# anvil_driver.net
KiCad netlist of a schematic drawn in EAGLE
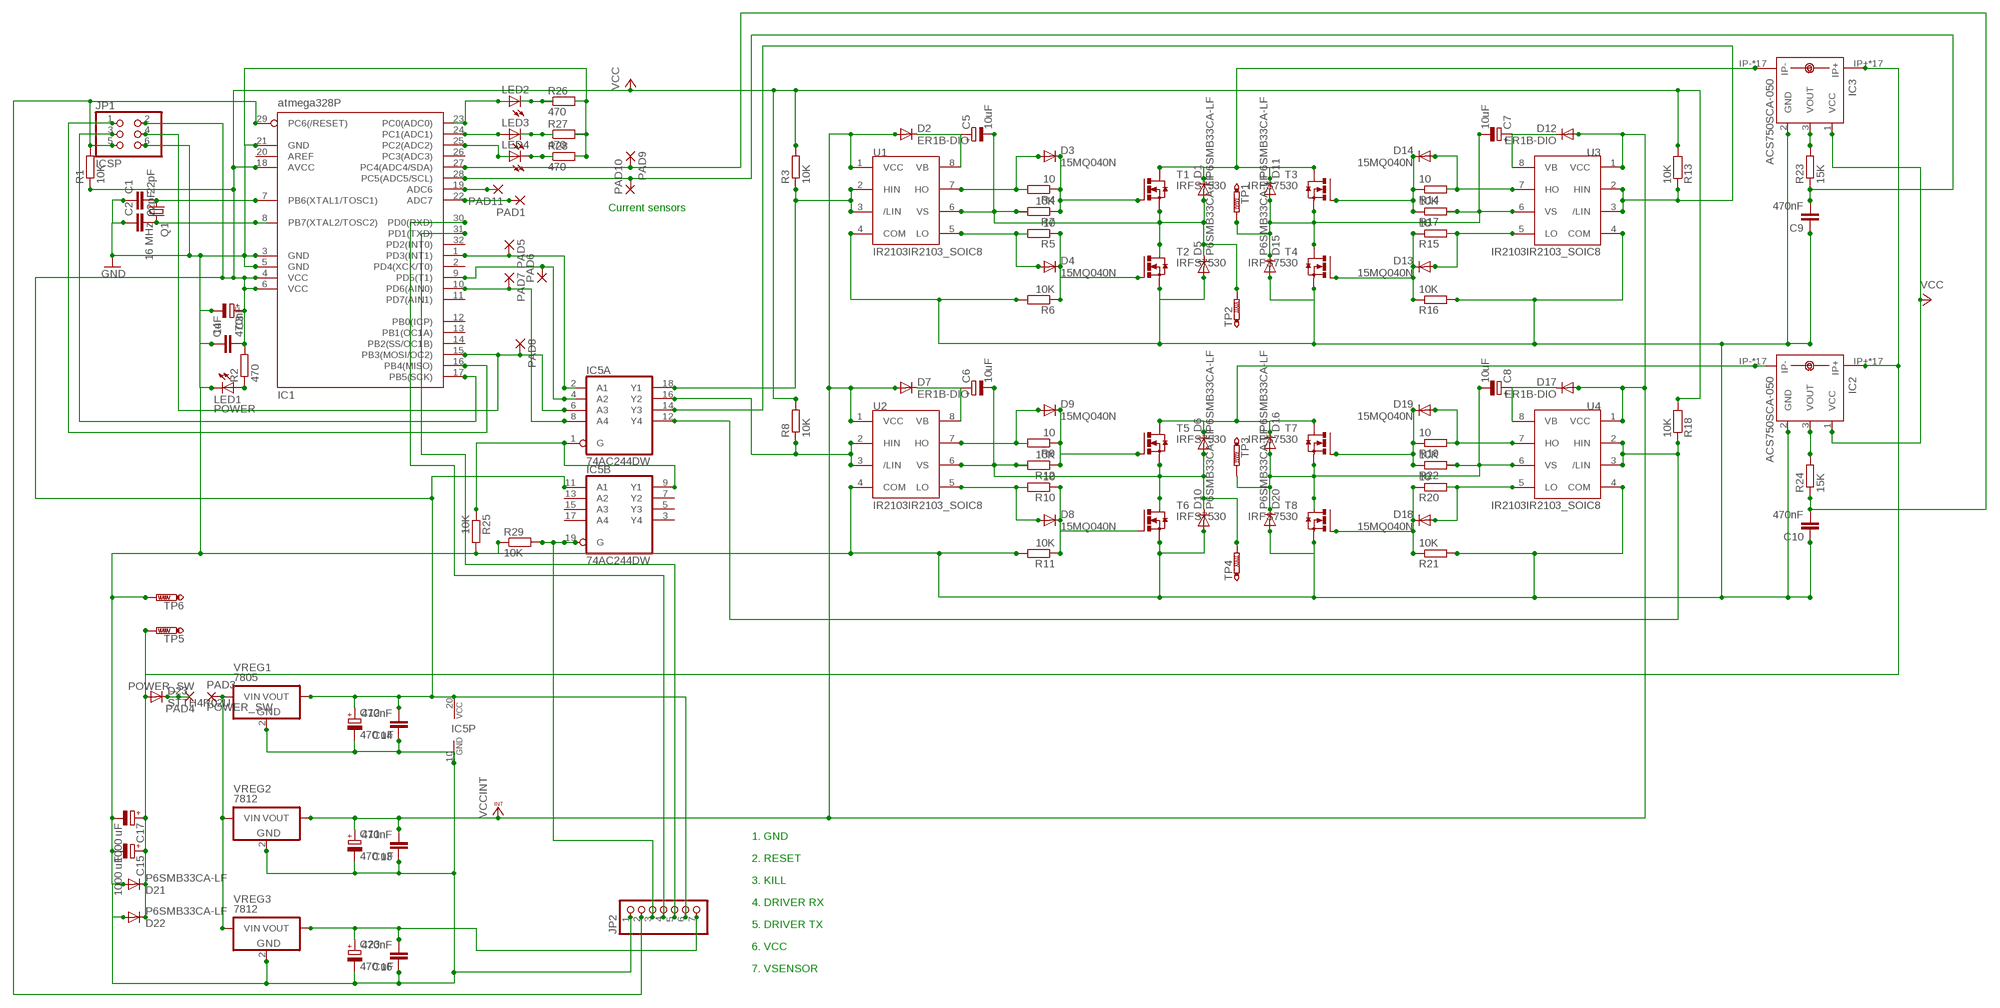
[diagram p0: schematic, sheet 1]

(export (version "E")
  (design (tool "Eeschema 10.0.6"))
  (components
    (comp (ref "C1")
      (value "22pF")
      (footprint "eagle-import:C1206")
      (libsource (lib "eagle-import") (part "C-EUC1206"))
    )
    (comp (ref "C2")
      (value "22pF")
      (footprint "eagle-import:C1206")
      (libsource (lib "eagle-import") (part "C-EUC1206"))
    )
    (comp (ref "C3")
      (value "1uF")
      (footprint "eagle-import:153CLV-0405")
      (libsource (lib "eagle-import") (part "CPOL-EU153CLV-0405"))
    )
    (comp (ref "C4")
      (value "470nF")
      (footprint "eagle-import:C1206")
      (libsource (lib "eagle-import") (part "C-EUC1206"))
    )
    (comp (ref "C5")
      (value "10uF")
      (footprint "eagle-import:153CLV-0405")
      (libsource (lib "eagle-import") (part "CPOL-EU153CLV-0405"))
    )
    (comp (ref "C6")
      (value "10uF")
      (footprint "eagle-import:153CLV-0405")
      (libsource (lib "eagle-import") (part "CPOL-EU153CLV-0405"))
    )
    (comp (ref "C7")
      (value "10uF")
      (footprint "eagle-import:153CLV-0405")
      (libsource (lib "eagle-import") (part "CPOL-EU153CLV-0405"))
    )
    (comp (ref "C8")
      (value "10uF")
      (footprint "eagle-import:153CLV-0405")
      (libsource (lib "eagle-import") (part "CPOL-EU153CLV-0405"))
    )
    (comp (ref "C9")
      (value "470nF")
      (footprint "eagle-import:C1206")
      (libsource (lib "eagle-import") (part "C-EUC1206"))
    )
    (comp (ref "C10")
      (value "470nF")
      (footprint "eagle-import:C1206")
      (libsource (lib "eagle-import") (part "C-EUC1206"))
    )
    (comp (ref "C11")
      (value "470 uF")
      (footprint "eagle-import:139CLL-2W")
      (libsource (lib "eagle-import") (part "CPOL-EU139CLL-2W"))
    )
    (comp (ref "C12")
      (value "470 uF")
      (footprint "eagle-import:139CLL-2W")
      (libsource (lib "eagle-import") (part "CPOL-EU139CLL-2W"))
    )
    (comp (ref "C13")
      (value "470nF")
      (footprint "eagle-import:C1206")
      (libsource (lib "eagle-import") (part "C-EUC1206"))
    )
    (comp (ref "C14")
      (value "470nF")
      (footprint "eagle-import:C1206")
      (libsource (lib "eagle-import") (part "C-EUC1206"))
    )
    (comp (ref "C15")
      (value "1000 uF")
      (footprint "eagle-import:139CLL-2W")
      (libsource (lib "eagle-import") (part "CPOL-EU139CLL-2W"))
    )
    (comp (ref "C16")
      (value "470nF")
      (footprint "eagle-import:C1206")
      (libsource (lib "eagle-import") (part "C-EUC1206"))
    )
    (comp (ref "C17")
      (value "1000 uF")
      (footprint "eagle-import:139CLL-2W")
      (libsource (lib "eagle-import") (part "CPOL-EU139CLL-2W"))
    )
    (comp (ref "C23")
      (value "470 uF")
      (footprint "eagle-import:139CLL-2W")
      (libsource (lib "eagle-import") (part "CPOL-EU139CLL-2W"))
    )
    (comp (ref "D1")
      (value "P6SMB33CA-LF")
      (footprint "eagle-import:DO214AA")
      (libsource (lib "eagle-import") (part "DIODE-DO214AA"))
    )
    (comp (ref "D2")
      (value "ER1B-DIO")
      (footprint "eagle-import:DO214AC")
      (libsource (lib "eagle-import") (part "DIODE-DO214AC"))
    )
    (comp (ref "D3")
      (value "15MQ040N")
      (footprint "eagle-import:DO214AC")
      (libsource (lib "eagle-import") (part "DIODE-DO214AC"))
    )
    (comp (ref "D4")
      (value "15MQ040N")
      (footprint "eagle-import:DO214AC")
      (libsource (lib "eagle-import") (part "DIODE-DO214AC"))
    )
    (comp (ref "D5")
      (value "P6SMB33CA-LF")
      (footprint "eagle-import:DO214AA")
      (libsource (lib "eagle-import") (part "DIODE-DO214AA"))
    )
    (comp (ref "D6")
      (value "P6SMB33CA-LF")
      (footprint "eagle-import:DO214AA")
      (libsource (lib "eagle-import") (part "DIODE-DO214AA"))
    )
    (comp (ref "D7")
      (value "ER1B-DIO")
      (footprint "eagle-import:DO214AC")
      (libsource (lib "eagle-import") (part "DIODE-DO214AC"))
    )
    (comp (ref "D8")
      (value "15MQ040N")
      (footprint "eagle-import:DO214AC")
      (libsource (lib "eagle-import") (part "DIODE-DO214AC"))
    )
    (comp (ref "D9")
      (value "15MQ040N")
      (footprint "eagle-import:DO214AC")
      (libsource (lib "eagle-import") (part "DIODE-DO214AC"))
    )
    (comp (ref "D10")
      (value "P6SMB33CA-LF")
      (footprint "eagle-import:DO214AA")
      (libsource (lib "eagle-import") (part "DIODE-DO214AA"))
    )
    (comp (ref "D11")
      (value "P6SMB33CA-LF")
      (footprint "eagle-import:DO214AA")
      (libsource (lib "eagle-import") (part "DIODE-DO214AA"))
    )
    (comp (ref "D12")
      (value "ER1B-DIO")
      (footprint "eagle-import:DO214AC")
      (libsource (lib "eagle-import") (part "DIODE-DO214AC"))
    )
    (comp (ref "D13")
      (value "15MQ040N")
      (footprint "eagle-import:DO214AC")
      (libsource (lib "eagle-import") (part "DIODE-DO214AC"))
    )
    (comp (ref "D14")
      (value "15MQ040N")
      (footprint "eagle-import:DO214AC")
      (libsource (lib "eagle-import") (part "DIODE-DO214AC"))
    )
    (comp (ref "D15")
      (value "P6SMB33CA-LF")
      (footprint "eagle-import:DO214AA")
      (libsource (lib "eagle-import") (part "DIODE-DO214AA"))
    )
    (comp (ref "D16")
      (value "P6SMB33CA-LF")
      (footprint "eagle-import:DO214AA")
      (libsource (lib "eagle-import") (part "DIODE-DO214AA"))
    )
    (comp (ref "D17")
      (value "ER1B-DIO")
      (footprint "eagle-import:DO214AC")
      (libsource (lib "eagle-import") (part "DIODE-DO214AC"))
    )
    (comp (ref "D18")
      (value "15MQ040N")
      (footprint "eagle-import:DO214AC")
      (libsource (lib "eagle-import") (part "DIODE-DO214AC"))
    )
    (comp (ref "D19")
      (value "15MQ040N")
      (footprint "eagle-import:DO214AC")
      (libsource (lib "eagle-import") (part "DIODE-DO214AC"))
    )
    (comp (ref "D20")
      (value "P6SMB33CA-LF")
      (footprint "eagle-import:DO214AA")
      (libsource (lib "eagle-import") (part "DIODE-DO214AA"))
    )
    (comp (ref "D21")
      (value "P6SMB33CA-LF")
      (footprint "eagle-import:DO214AA")
      (libsource (lib "eagle-import") (part "DIODE-DO214AA"))
    )
    (comp (ref "D22")
      (value "P6SMB33CA-LF")
      (footprint "eagle-import:DO214AA")
      (libsource (lib "eagle-import") (part "DIODE-DO214AA"))
    )
    (comp (ref "D23")
      (value "STTH4R02U")
      (footprint "eagle-import:DO214AA")
      (libsource (lib "eagle-import") (part "DIODE-DO214AA"))
    )
    (comp (ref "IC1")
      (value "atmega328P")
      (footprint "eagle-import:TQFP32-08")
      (fields (field (name "MPN") "ATMEGA8-16AU"))
      (libsource (lib "eagle-import") (part "MEGA8-AI"))
    )
    (comp (ref "IC2")
      (value "ACS750SCA-050")
      (footprint "eagle-import:ACS75050")
      (fields (field (name "MF") "ALLEGRO MICROSYSTEMS, INC."))
      (libsource (lib "eagle-import") (part "ACS750CA-050S"))
    )
    (comp (ref "IC3")
      (value "ACS750SCA-050")
      (footprint "eagle-import:ACS75050")
      (fields (field (name "MF") "ALLEGRO MICROSYSTEMS, INC."))
      (libsource (lib "eagle-import") (part "ACS750CA-050S"))
    )
    (comp (ref "IC5")
      (value "74AC244DW")
      (footprint "eagle-import:SO20W")
      (libsource (lib "eagle-import") (part "74244DWAC"))
    )
    (comp (ref "JP1")
      (value "ICSP")
      (footprint "eagle-import:2X03SMD")
      (libsource (lib "eagle-import") (part "PINHD-2X3_2.54-SMD"))
    )
    (comp (ref "JP2")
      (value "PINHD-1X7_2.54")
      (footprint "eagle-import:1X07")
      (libsource (lib "eagle-import") (part "PINHD-1X7_2.54"))
    )
    (comp (ref "LED1")
      (value "POWER")
      (footprint "eagle-import:1206")
      (libsource (lib "eagle-import") (part "LEDSMT1206"))
    )
    (comp (ref "LED2")
      (value "LEDSMT1206")
      (footprint "eagle-import:1206")
      (libsource (lib "eagle-import") (part "LEDSMT1206"))
    )
    (comp (ref "LED3")
      (value "LEDSMT1206")
      (footprint "eagle-import:1206")
      (libsource (lib "eagle-import") (part "LEDSMT1206"))
    )
    (comp (ref "LED4")
      (value "LEDSMT1206")
      (footprint "eagle-import:1206")
      (libsource (lib "eagle-import") (part "LEDSMT1206"))
    )
    (comp (ref "PAD1")
      (value "SMD2")
      (footprint "eagle-import:SMD1,27-2,54")
      (libsource (lib "eagle-import") (part "SMD2"))
    )
    (comp (ref "PAD3")
      (value "POWER_SW")
      (footprint "eagle-import:1,6_0,8")
      (libsource (lib "eagle-import") (part "1,6/0,8"))
    )
    (comp (ref "PAD4")
      (value "POWER_SW")
      (footprint "eagle-import:1,6_0,8")
      (libsource (lib "eagle-import") (part "1,6/0,8"))
    )
    (comp (ref "PAD5")
      (value "SMD2")
      (footprint "eagle-import:SMD1,27-2,54")
      (libsource (lib "eagle-import") (part "SMD2"))
    )
    (comp (ref "PAD6")
      (value "SMD2")
      (footprint "eagle-import:SMD1,27-2,54")
      (libsource (lib "eagle-import") (part "SMD2"))
    )
    (comp (ref "PAD7")
      (value "SMD2")
      (footprint "eagle-import:SMD1,27-2,54")
      (libsource (lib "eagle-import") (part "SMD2"))
    )
    (comp (ref "PAD8")
      (value "SMD2")
      (footprint "eagle-import:SMD1,27-2,54")
      (libsource (lib "eagle-import") (part "SMD2"))
    )
    (comp (ref "PAD9")
      (value "SMD2")
      (footprint "eagle-import:SMD1,27-2,54")
      (libsource (lib "eagle-import") (part "SMD2"))
    )
    (comp (ref "PAD10")
      (value "SMD2")
      (footprint "eagle-import:SMD1,27-2,54")
      (libsource (lib "eagle-import") (part "SMD2"))
    )
    (comp (ref "PAD11")
      (value "SMD2")
      (footprint "eagle-import:SMD1,27-2,54")
      (libsource (lib "eagle-import") (part "SMD2"))
    )
    (comp (ref "Q1")
      (value "16 MHz")
      (footprint "eagle-import:CSM-7X-DU")
      (libsource (lib "eagle-import") (part "CSM-7X-DU"))
    )
    (comp (ref "R1")
      (value "10K")
      (footprint "eagle-import:M1206")
      (libsource (lib "eagle-import") (part "R-EU_M1206"))
    )
    (comp (ref "R2")
      (value "470")
      (footprint "eagle-import:M1206")
      (libsource (lib "eagle-import") (part "R-EU_M1206"))
    )
    (comp (ref "R3")
      (value "10K")
      (footprint "eagle-import:M1206")
      (libsource (lib "eagle-import") (part "R-EU_M1206"))
    )
    (comp (ref "R4")
      (value "10")
      (footprint "eagle-import:M1206")
      (libsource (lib "eagle-import") (part "R-EU_M1206"))
    )
    (comp (ref "R5")
      (value "10")
      (footprint "eagle-import:M1206")
      (libsource (lib "eagle-import") (part "R-EU_M1206"))
    )
    (comp (ref "R6")
      (value "10K")
      (footprint "eagle-import:M1206")
      (libsource (lib "eagle-import") (part "R-EU_M1206"))
    )
    (comp (ref "R7")
      (value "10K")
      (footprint "eagle-import:M1206")
      (libsource (lib "eagle-import") (part "R-EU_M1206"))
    )
    (comp (ref "R8")
      (value "10K")
      (footprint "eagle-import:M1206")
      (libsource (lib "eagle-import") (part "R-EU_M1206"))
    )
    (comp (ref "R9")
      (value "10")
      (footprint "eagle-import:M1206")
      (libsource (lib "eagle-import") (part "R-EU_M1206"))
    )
    (comp (ref "R10")
      (value "10")
      (footprint "eagle-import:M1206")
      (libsource (lib "eagle-import") (part "R-EU_M1206"))
    )
    (comp (ref "R11")
      (value "10K")
      (footprint "eagle-import:M1206")
      (libsource (lib "eagle-import") (part "R-EU_M1206"))
    )
    (comp (ref "R12")
      (value "10K")
      (footprint "eagle-import:M1206")
      (libsource (lib "eagle-import") (part "R-EU_M1206"))
    )
    (comp (ref "R13")
      (value "10K")
      (footprint "eagle-import:M1206")
      (libsource (lib "eagle-import") (part "R-EU_M1206"))
    )
    (comp (ref "R14")
      (value "10")
      (footprint "eagle-import:M1206")
      (libsource (lib "eagle-import") (part "R-EU_M1206"))
    )
    (comp (ref "R15")
      (value "10")
      (footprint "eagle-import:M1206")
      (libsource (lib "eagle-import") (part "R-EU_M1206"))
    )
    (comp (ref "R16")
      (value "10K")
      (footprint "eagle-import:M1206")
      (libsource (lib "eagle-import") (part "R-EU_M1206"))
    )
    (comp (ref "R17")
      (value "10K")
      (footprint "eagle-import:M1206")
      (libsource (lib "eagle-import") (part "R-EU_M1206"))
    )
    (comp (ref "R18")
      (value "10K")
      (footprint "eagle-import:M1206")
      (libsource (lib "eagle-import") (part "R-EU_M1206"))
    )
    (comp (ref "R19")
      (value "10")
      (footprint "eagle-import:M1206")
      (libsource (lib "eagle-import") (part "R-EU_M1206"))
    )
    (comp (ref "R20")
      (value "10")
      (footprint "eagle-import:M1206")
      (libsource (lib "eagle-import") (part "R-EU_M1206"))
    )
    (comp (ref "R21")
      (value "10K")
      (footprint "eagle-import:M1206")
      (libsource (lib "eagle-import") (part "R-EU_M1206"))
    )
    (comp (ref "R22")
      (value "10K")
      (footprint "eagle-import:M1206")
      (libsource (lib "eagle-import") (part "R-EU_M1206"))
    )
    (comp (ref "R23")
      (value "15K")
      (footprint "eagle-import:M1206")
      (libsource (lib "eagle-import") (part "R-EU_M1206"))
    )
    (comp (ref "R24")
      (value "15K")
      (footprint "eagle-import:M1206")
      (libsource (lib "eagle-import") (part "R-EU_M1206"))
    )
    (comp (ref "R25")
      (value "10K")
      (footprint "eagle-import:M1206")
      (libsource (lib "eagle-import") (part "R-EU_M1206"))
    )
    (comp (ref "R26")
      (value "470")
      (footprint "eagle-import:M1206")
      (libsource (lib "eagle-import") (part "R-EU_M1206"))
    )
    (comp (ref "R27")
      (value "470")
      (footprint "eagle-import:M1206")
      (libsource (lib "eagle-import") (part "R-EU_M1206"))
    )
    (comp (ref "R28")
      (value "470")
      (footprint "eagle-import:M1206")
      (libsource (lib "eagle-import") (part "R-EU_M1206"))
    )
    (comp (ref "R29")
      (value "10K")
      (footprint "eagle-import:M1206")
      (libsource (lib "eagle-import") (part "R-EU_M1206"))
    )
    (comp (ref "T1")
      (value "IRFS7530")
      (footprint "eagle-import:DDPAK7")
      (libsource (lib "eagle-import") (part "IRF3805S"))
    )
    (comp (ref "T2")
      (value "IRFS7530")
      (footprint "eagle-import:DDPAK7")
      (libsource (lib "eagle-import") (part "IRF3805S"))
    )
    (comp (ref "T3")
      (value "IRFS7530")
      (footprint "eagle-import:DDPAK7")
      (libsource (lib "eagle-import") (part "IRF3805S"))
    )
    (comp (ref "T4")
      (value "IRFS7530")
      (footprint "eagle-import:DDPAK7")
      (libsource (lib "eagle-import") (part "IRF3805S"))
    )
    (comp (ref "T5")
      (value "IRFS7530")
      (footprint "eagle-import:DDPAK7")
      (libsource (lib "eagle-import") (part "IRF3805S"))
    )
    (comp (ref "T6")
      (value "IRFS7530")
      (footprint "eagle-import:DDPAK7")
      (libsource (lib "eagle-import") (part "IRF3805S"))
    )
    (comp (ref "T7")
      (value "IRFS7530")
      (footprint "eagle-import:DDPAK7")
      (libsource (lib "eagle-import") (part "IRF3805S"))
    )
    (comp (ref "T8")
      (value "IRFS7530")
      (footprint "eagle-import:DDPAK7")
      (libsource (lib "eagle-import") (part "IRF3805S"))
    )
    (comp (ref "TP1")
      (value "PTR1PAD1-20")
      (footprint "eagle-import:P1-20")
      (libsource (lib "eagle-import") (part "PTR1PAD1-20"))
    )
    (comp (ref "TP2")
      (value "PTR1PAD1-20")
      (footprint "eagle-import:P1-20")
      (libsource (lib "eagle-import") (part "PTR1PAD1-20"))
    )
    (comp (ref "TP3")
      (value "PTR1PAD1-20")
      (footprint "eagle-import:P1-20")
      (libsource (lib "eagle-import") (part "PTR1PAD1-20"))
    )
    (comp (ref "TP4")
      (value "PTR1PAD1-20")
      (footprint "eagle-import:P1-20")
      (libsource (lib "eagle-import") (part "PTR1PAD1-20"))
    )
    (comp (ref "TP5")
      (value "PTR1PAD1-20")
      (footprint "eagle-import:P1-20")
      (libsource (lib "eagle-import") (part "PTR1PAD1-20"))
    )
    (comp (ref "TP6")
      (value "PTR1PAD1-20")
      (footprint "eagle-import:P1-20")
      (libsource (lib "eagle-import") (part "PTR1PAD1-20"))
    )
    (comp (ref "U1")
      (value "IR2103IR2103_SOIC8")
      (footprint "eagle-import:SO08")
      (libsource (lib "eagle-import") (part "IR2103IR2103_SOIC8"))
    )
    (comp (ref "U2")
      (value "IR2103IR2103_SOIC8")
      (footprint "eagle-import:SO08")
      (libsource (lib "eagle-import") (part "IR2103IR2103_SOIC8"))
    )
    (comp (ref "U3")
      (value "IR2103IR2103_SOIC8")
      (footprint "eagle-import:SO08")
      (libsource (lib "eagle-import") (part "IR2103IR2103_SOIC8"))
    )
    (comp (ref "U4")
      (value "IR2103IR2103_SOIC8")
      (footprint "eagle-import:SO08")
      (libsource (lib "eagle-import") (part "IR2103IR2103_SOIC8"))
    )
    (comp (ref "VREG1")
      (value "7805")
      (footprint "eagle-import:D2PAK")
      (libsource (lib "eagle-import") (part "VREG_3PINS-D2PAK"))
    )
    (comp (ref "VREG2")
      (value "7812")
      (footprint "eagle-import:D2PAK")
      (libsource (lib "eagle-import") (part "VREG_3PINS-D2PAK"))
    )
    (comp (ref "VREG3")
      (value "7812")
      (footprint "eagle-import:D2PAK")
      (libsource (lib "eagle-import") (part "VREG_3PINS-D2PAK"))
    )
  )
  (nets
    (net (code "1") (name "/VB_1") (class "Default")
      (node (ref "C5") (pin "+") (pinfunction "+_+") (pintype "passive"))
      (node (ref "D2") (pin "C") (pinfunction "C_C") (pintype "passive"))
      (node (ref "U1") (pin "8") (pinfunction "VB_8") (pintype "power_in"))
    )
    (net (code "2") (name "/VB_2") (class "Default")
      (node (ref "C7") (pin "+") (pinfunction "+_+") (pintype "passive"))
      (node (ref "D12") (pin "C") (pinfunction "C_C") (pintype "passive"))
      (node (ref "U3") (pin "8") (pinfunction "VB_8") (pintype "power_in"))
    )
    (net (code "3") (name "/VB_3") (class "Default")
      (node (ref "C8") (pin "+") (pinfunction "+_+") (pintype "passive"))
      (node (ref "D17") (pin "C") (pinfunction "C_C") (pintype "passive"))
      (node (ref "U4") (pin "8") (pinfunction "VB_8") (pintype "power_in"))
    )
    (net (code "4") (name "/VB_4") (class "Default")
      (node (ref "C6") (pin "+") (pinfunction "+_+") (pintype "passive"))
      (node (ref "D7") (pin "C") (pinfunction "C_C") (pintype "passive"))
      (node (ref "U2") (pin "8") (pinfunction "VB_8") (pintype "power_in"))
    )
    (net (code "5") (name "GND") (class "Default")
      (node (ref "C1") (pin "1") (pinfunction "1_1") (pintype "passive"))
      (node (ref "C10") (pin "1") (pinfunction "1_1") (pintype "passive"))
      (node (ref "C11") (pin "-") (pinfunction "-_-") (pintype "passive"))
      (node (ref "C12") (pin "-") (pinfunction "-_-") (pintype "passive"))
      (node (ref "C13") (pin "1") (pinfunction "1_1") (pintype "passive"))
      (node (ref "C14") (pin "1") (pinfunction "1_1") (pintype "passive"))
      (node (ref "C15") (pin "-") (pinfunction "-_-") (pintype "passive"))
      (node (ref "C16") (pin "1") (pinfunction "1_1") (pintype "passive"))
      (node (ref "C17") (pin "-") (pinfunction "-_-") (pintype "passive"))
      (node (ref "C2") (pin "1") (pinfunction "1_1") (pintype "passive"))
      (node (ref "C23") (pin "-") (pinfunction "-_-") (pintype "passive"))
      (node (ref "C3") (pin "-") (pinfunction "-_-") (pintype "passive"))
      (node (ref "C4") (pin "1") (pinfunction "1_1") (pintype "passive"))
      (node (ref "C9") (pin "1") (pinfunction "1_1") (pintype "passive"))
      (node (ref "D10") (pin "A") (pinfunction "A_A") (pintype "passive"))
      (node (ref "D15") (pin "A") (pinfunction "A_A") (pintype "passive"))
      (node (ref "D20") (pin "A") (pinfunction "A_A") (pintype "passive"))
      (node (ref "D21") (pin "A") (pinfunction "A_A") (pintype "passive"))
      (node (ref "D22") (pin "A") (pinfunction "A_A") (pintype "passive"))
      (node (ref "D5") (pin "A") (pinfunction "A_A") (pintype "passive"))
      (node (ref "IC1") (pin "21") (pinfunction "GND_21") (pintype "power_in"))
      (node (ref "IC1") (pin "3") (pinfunction "GND_3") (pintype "power_in"))
      (node (ref "IC1") (pin "5") (pinfunction "GND_5") (pintype "power_in"))
      (node (ref "IC2") (pin "2") (pinfunction "GND_2") (pintype "power_in"))
      (node (ref "IC3") (pin "2") (pinfunction "GND_2") (pintype "power_in"))
      (node (ref "IC5") (pin "10") (pinfunction "GND_10") (pintype "power_in"))
      (node (ref "JP1") (pin "6") (pinfunction "6_6") (pintype "passive"))
      (node (ref "JP2") (pin "1") (pinfunction "1_1") (pintype "passive"))
      (node (ref "LED1") (pin "C") (pinfunction "C_C") (pintype "passive"))
      (node (ref "R11") (pin "2") (pinfunction "2_2") (pintype "passive"))
      (node (ref "R16") (pin "2") (pinfunction "2_2") (pintype "passive"))
      (node (ref "R21") (pin "2") (pinfunction "2_2") (pintype "passive"))
      (node (ref "R25") (pin "2") (pinfunction "2_2") (pintype "passive"))
      (node (ref "R26") (pin "2") (pinfunction "2_2") (pintype "passive"))
      (node (ref "R27") (pin "2") (pinfunction "2_2") (pintype "passive"))
      (node (ref "R28") (pin "2") (pinfunction "2_2") (pintype "passive"))
      (node (ref "R29") (pin "1") (pinfunction "1_1") (pintype "passive"))
      (node (ref "R6") (pin "2") (pinfunction "2_2") (pintype "passive"))
      (node (ref "T2") (pin "2") (pinfunction "S_2") (pintype "passive"))
      (node (ref "T2") (pin "3") (pinfunction "S_3") (pintype "passive"))
      (node (ref "T2") (pin "5") (pinfunction "S_5") (pintype "passive"))
      (node (ref "T2") (pin "6") (pinfunction "S_6") (pintype "passive"))
      (node (ref "T2") (pin "7") (pinfunction "S_7") (pintype "passive"))
      (node (ref "T4") (pin "2") (pinfunction "S_2") (pintype "passive"))
      (node (ref "T4") (pin "3") (pinfunction "S_3") (pintype "passive"))
      (node (ref "T4") (pin "5") (pinfunction "S_5") (pintype "passive"))
      (node (ref "T4") (pin "6") (pinfunction "S_6") (pintype "passive"))
      (node (ref "T4") (pin "7") (pinfunction "S_7") (pintype "passive"))
      (node (ref "T6") (pin "2") (pinfunction "S_2") (pintype "passive"))
      (node (ref "T6") (pin "3") (pinfunction "S_3") (pintype "passive"))
      (node (ref "T6") (pin "5") (pinfunction "S_5") (pintype "passive"))
      (node (ref "T6") (pin "6") (pinfunction "S_6") (pintype "passive"))
      (node (ref "T6") (pin "7") (pinfunction "S_7") (pintype "passive"))
      (node (ref "T8") (pin "2") (pinfunction "S_2") (pintype "passive"))
      (node (ref "T8") (pin "3") (pinfunction "S_3") (pintype "passive"))
      (node (ref "T8") (pin "5") (pinfunction "S_5") (pintype "passive"))
      (node (ref "T8") (pin "6") (pinfunction "S_6") (pintype "passive"))
      (node (ref "T8") (pin "7") (pinfunction "S_7") (pintype "passive"))
      (node (ref "TP6") (pin "TP") (pinfunction "TP_TP") (pintype "input"))
      (node (ref "U1") (pin "4") (pinfunction "COM_4") (pintype "power_in"))
      (node (ref "U2") (pin "4") (pinfunction "COM_4") (pintype "power_in"))
      (node (ref "U3") (pin "4") (pinfunction "COM_4") (pintype "power_in"))
      (node (ref "U4") (pin "4") (pinfunction "COM_4") (pintype "power_in"))
      (node (ref "VREG1") (pin "2") (pinfunction "GND_2") (pintype "bidirectional"))
      (node (ref "VREG2") (pin "2") (pinfunction "GND_2") (pintype "bidirectional"))
      (node (ref "VREG3") (pin "2") (pinfunction "GND_2") (pintype "bidirectional"))
    )
    (net (code "6") (name "Net-(C15-Pad+)") (class "Default")
      (node (ref "C15") (pin "+") (pinfunction "+_+") (pintype "passive"))
      (node (ref "C17") (pin "+") (pinfunction "+_+") (pintype "passive"))
      (node (ref "D21") (pin "C") (pinfunction "C_C") (pintype "passive"))
      (node (ref "D22") (pin "C") (pinfunction "C_C") (pintype "passive"))
      (node (ref "D23") (pin "A") (pinfunction "A_A") (pintype "passive"))
      (node (ref "IC2") (pin "IP+") (pinfunction "IP+_IP+") (pintype "passive"))
      (node (ref "IC2") (pin "IP+@10") (pinfunction "IP+_IP+@10") (pintype "passive"))
      (node (ref "IC2") (pin "IP+@11") (pinfunction "IP+_IP+@11") (pintype "passive"))
      (node (ref "IC2") (pin "IP+@12") (pinfunction "IP+_IP+@12") (pintype "passive"))
      (node (ref "IC2") (pin "IP+@13") (pinfunction "IP+_IP+@13") (pintype "passive"))
      (node (ref "IC2") (pin "IP+@14") (pinfunction "IP+_IP+@14") (pintype "passive"))
      (node (ref "IC2") (pin "IP+@15") (pinfunction "IP+_IP+@15") (pintype "passive"))
      (node (ref "IC2") (pin "IP+@16") (pinfunction "IP+_IP+@16") (pintype "passive"))
      (node (ref "IC2") (pin "IP+@17") (pinfunction "IP+_IP+@17") (pintype "passive"))
      (node (ref "IC2") (pin "IP+@2") (pinfunction "IP+_IP+@2") (pintype "passive"))
      (node (ref "IC2") (pin "IP+@3") (pinfunction "IP+_IP+@3") (pintype "passive"))
      (node (ref "IC2") (pin "IP+@4") (pinfunction "IP+_IP+@4") (pintype "passive"))
      (node (ref "IC2") (pin "IP+@5") (pinfunction "IP+_IP+@5") (pintype "passive"))
      (node (ref "IC2") (pin "IP+@6") (pinfunction "IP+_IP+@6") (pintype "passive"))
      (node (ref "IC2") (pin "IP+@7") (pinfunction "IP+_IP+@7") (pintype "passive"))
      (node (ref "IC2") (pin "IP+@8") (pinfunction "IP+_IP+@8") (pintype "passive"))
      (node (ref "IC2") (pin "IP+@9") (pinfunction "IP+_IP+@9") (pintype "passive"))
      (node (ref "IC3") (pin "IP+") (pinfunction "IP+_IP+") (pintype "passive"))
      (node (ref "IC3") (pin "IP+@10") (pinfunction "IP+_IP+@10") (pintype "passive"))
      (node (ref "IC3") (pin "IP+@11") (pinfunction "IP+_IP+@11") (pintype "passive"))
      (node (ref "IC3") (pin "IP+@12") (pinfunction "IP+_IP+@12") (pintype "passive"))
      (node (ref "IC3") (pin "IP+@13") (pinfunction "IP+_IP+@13") (pintype "passive"))
      (node (ref "IC3") (pin "IP+@14") (pinfunction "IP+_IP+@14") (pintype "passive"))
      (node (ref "IC3") (pin "IP+@15") (pinfunction "IP+_IP+@15") (pintype "passive"))
      (node (ref "IC3") (pin "IP+@16") (pinfunction "IP+_IP+@16") (pintype "passive"))
      (node (ref "IC3") (pin "IP+@17") (pinfunction "IP+_IP+@17") (pintype "passive"))
      (node (ref "IC3") (pin "IP+@2") (pinfunction "IP+_IP+@2") (pintype "passive"))
      (node (ref "IC3") (pin "IP+@3") (pinfunction "IP+_IP+@3") (pintype "passive"))
      (node (ref "IC3") (pin "IP+@4") (pinfunction "IP+_IP+@4") (pintype "passive"))
      (node (ref "IC3") (pin "IP+@5") (pinfunction "IP+_IP+@5") (pintype "passive"))
      (node (ref "IC3") (pin "IP+@6") (pinfunction "IP+_IP+@6") (pintype "passive"))
      (node (ref "IC3") (pin "IP+@7") (pinfunction "IP+_IP+@7") (pintype "passive"))
      (node (ref "IC3") (pin "IP+@8") (pinfunction "IP+_IP+@8") (pintype "passive"))
      (node (ref "IC3") (pin "IP+@9") (pinfunction "IP+_IP+@9") (pintype "passive"))
      (node (ref "TP5") (pin "TP") (pinfunction "TP_TP") (pintype "input"))
    )
    (net (code "7") (name "Net-(IC1-ADC6)") (class "Default")
      (node (ref "IC1") (pin "19") (pinfunction "ADC6_19") (pintype "bidirectional"))
      (node (ref "PAD11") (pin "1") (pinfunction "P_1") (pintype "passive"))
    )
    (net (code "8") (name "Net-(IC1-ADC7)") (class "Default")
      (node (ref "IC1") (pin "22") (pinfunction "ADC7_22") (pintype "bidirectional"))
      (node (ref "PAD1") (pin "1") (pinfunction "P_1") (pintype "passive"))
    )
    (net (code "9") (name "Net-(IC1-PB3(MOSI{slash}OC2))") (class "Default")
      (node (ref "IC1") (pin "15") (pinfunction "PB3(MOSI/OC2)_15") (pintype "bidirectional"))
      (node (ref "IC5") (pin "6") (pinfunction "A3_6") (pintype "input"))
      (node (ref "JP1") (pin "4") (pinfunction "4_4") (pintype "passive"))
      (node (ref "PAD8") (pin "1") (pinfunction "P_1") (pintype "passive"))
    )
    (net (code "10") (name "Net-(IC1-PB4(MISO))") (class "Default")
      (node (ref "IC1") (pin "16") (pinfunction "PB4(MISO)_16") (pintype "bidirectional"))
      (node (ref "JP1") (pin "1") (pinfunction "1_1") (pintype "passive"))
    )
    (net (code "11") (name "Net-(IC1-PB5(SCK))") (class "Default")
      (node (ref "IC1") (pin "17") (pinfunction "PB5(SCK)_17") (pintype "bidirectional"))
      (node (ref "JP1") (pin "3") (pinfunction "3_3") (pintype "passive"))
    )
    (net (code "12") (name "Net-(IC1-PB6(XTAL1{slash}TOSC1))") (class "Default")
      (node (ref "C1") (pin "2") (pinfunction "2_2") (pintype "passive"))
      (node (ref "IC1") (pin "7") (pinfunction "PB6(XTAL1/TOSC1)_7") (pintype "bidirectional"))
      (node (ref "Q1") (pin "1") (pinfunction "1_1") (pintype "passive"))
    )
    (net (code "13") (name "Net-(IC1-PB7(XTAL2{slash}TOSC2))") (class "Default")
      (node (ref "C2") (pin "2") (pinfunction "2_2") (pintype "passive"))
      (node (ref "IC1") (pin "8") (pinfunction "PB7(XTAL2/TOSC2)_8") (pintype "bidirectional"))
      (node (ref "Q1") (pin "2") (pinfunction "2_2") (pintype "passive"))
    )
    (net (code "14") (name "Net-(IC1-PC0(ADC0))") (class "Default")
      (node (ref "IC1") (pin "23") (pinfunction "PC0(ADC0)_23") (pintype "bidirectional"))
      (node (ref "LED2") (pin "A") (pinfunction "A_A") (pintype "passive"))
    )
    (net (code "15") (name "Net-(IC1-PC1(ADC1))") (class "Default")
      (node (ref "IC1") (pin "24") (pinfunction "PC1(ADC1)_24") (pintype "bidirectional"))
      (node (ref "LED3") (pin "A") (pinfunction "A_A") (pintype "passive"))
    )
    (net (code "16") (name "Net-(IC1-PC2(ADC2))") (class "Default")
      (node (ref "IC1") (pin "25") (pinfunction "PC2(ADC2)_25") (pintype "bidirectional"))
      (node (ref "LED4") (pin "A") (pinfunction "A_A") (pintype "passive"))
    )
    (net (code "17") (name "Net-(IC1-PC4(ADC4{slash}SDA))") (class "Default")
      (node (ref "C10") (pin "2") (pinfunction "2_2") (pintype "passive"))
      (node (ref "IC1") (pin "27") (pinfunction "PC4(ADC4/SDA)_27") (pintype "bidirectional"))
      (node (ref "PAD9") (pin "1") (pinfunction "P_1") (pintype "passive"))
      (node (ref "R24") (pin "1") (pinfunction "1_1") (pintype "passive"))
    )
    (net (code "18") (name "Net-(IC1-PC5(ADC5{slash}SCL))") (class "Default")
      (node (ref "C9") (pin "2") (pinfunction "2_2") (pintype "passive"))
      (node (ref "IC1") (pin "28") (pinfunction "PC5(ADC5/SCL)_28") (pintype "bidirectional"))
      (node (ref "PAD10") (pin "1") (pinfunction "P_1") (pintype "passive"))
      (node (ref "R23") (pin "1") (pinfunction "1_1") (pintype "passive"))
    )
    (net (code "19") (name "Net-(IC1-PC6({slash}RESET))") (class "Default")
      (node (ref "IC1") (pin "29") (pinfunction "PC6(/RESET)_29") (pintype "bidirectional"))
      (node (ref "JP1") (pin "5") (pinfunction "5_5") (pintype "passive"))
      (node (ref "JP2") (pin "2") (pinfunction "2_2") (pintype "passive"))
      (node (ref "R1") (pin "2") (pinfunction "2_2") (pintype "passive"))
    )
    (net (code "20") (name "Net-(IC1-PD0(RXD))") (class "Default")
      (node (ref "IC1") (pin "30") (pinfunction "PD0(RXD)_30") (pintype "bidirectional"))
      (node (ref "JP2") (pin "4") (pinfunction "4_4") (pintype "passive"))
    )
    (net (code "21") (name "Net-(IC1-PD3(INT1))") (class "Default")
      (node (ref "IC1") (pin "1") (pinfunction "PD3(INT1)_1") (pintype "bidirectional"))
      (node (ref "IC5") (pin "2") (pinfunction "A1_2") (pintype "input"))
      (node (ref "PAD5") (pin "1") (pinfunction "P_1") (pintype "passive"))
    )
    (net (code "22") (name "Net-(IC1-PD5(T1))") (class "Default")
      (node (ref "IC1") (pin "9") (pinfunction "PD5(T1)_9") (pintype "bidirectional"))
      (node (ref "IC5") (pin "4") (pinfunction "A2_4") (pintype "input"))
      (node (ref "PAD6") (pin "1") (pinfunction "P_1") (pintype "passive"))
    )
    (net (code "23") (name "Net-(IC1-PD6(AIN0))") (class "Default")
      (node (ref "IC1") (pin "10") (pinfunction "PD6(AIN0)_10") (pintype "bidirectional"))
      (node (ref "IC5") (pin "8") (pinfunction "A4_8") (pintype "input"))
      (node (ref "PAD7") (pin "1") (pinfunction "P_1") (pintype "passive"))
    )
    (net (code "24") (name "Net-(IC2-VOUT)") (class "Default")
      (node (ref "IC2") (pin "3") (pinfunction "VOUT_3") (pintype "output"))
      (node (ref "R24") (pin "2") (pinfunction "2_2") (pintype "passive"))
    )
    (net (code "25") (name "Net-(IC3-VOUT)") (class "Default")
      (node (ref "IC3") (pin "3") (pinfunction "VOUT_3") (pintype "output"))
      (node (ref "R23") (pin "2") (pinfunction "2_2") (pintype "passive"))
    )
    (net (code "26") (name "Net-(IC5A-G)") (class "Default")
      (node (ref "IC5") (pin "1") (pinfunction "G_1") (pintype "input"))
      (node (ref "IC5") (pin "9") (pinfunction "Y1_9") (pintype "tri_state"))
      (node (ref "R25") (pin "1") (pinfunction "1_1") (pintype "passive"))
    )
    (net (code "27") (name "Net-(IC5A-Y1)") (class "Default")
      (node (ref "IC5") (pin "18") (pinfunction "Y1_18") (pintype "tri_state"))
      (node (ref "R3") (pin "1") (pinfunction "1_1") (pintype "passive"))
      (node (ref "U1") (pin "2") (pinfunction "HIN_2") (pintype "input"))
      (node (ref "U1") (pin "3") (pinfunction "/LIN_3") (pintype "input"))
    )
    (net (code "28") (name "Net-(IC5A-Y2)") (class "Default")
      (node (ref "IC5") (pin "16") (pinfunction "Y2_16") (pintype "tri_state"))
      (node (ref "R8") (pin "1") (pinfunction "1_1") (pintype "passive"))
      (node (ref "U2") (pin "2") (pinfunction "HIN_2") (pintype "input"))
      (node (ref "U2") (pin "3") (pinfunction "/LIN_3") (pintype "input"))
    )
    (net (code "29") (name "Net-(IC5A-Y3)") (class "Default")
      (node (ref "IC5") (pin "14") (pinfunction "Y3_14") (pintype "tri_state"))
      (node (ref "R13") (pin "1") (pinfunction "1_1") (pintype "passive"))
      (node (ref "U3") (pin "2") (pinfunction "HIN_2") (pintype "input"))
      (node (ref "U3") (pin "3") (pinfunction "/LIN_3") (pintype "input"))
    )
    (net (code "30") (name "Net-(IC5A-Y4)") (class "Default")
      (node (ref "IC5") (pin "12") (pinfunction "Y4_12") (pintype "tri_state"))
      (node (ref "R18") (pin "1") (pinfunction "1_1") (pintype "passive"))
      (node (ref "U4") (pin "2") (pinfunction "HIN_2") (pintype "input"))
      (node (ref "U4") (pin "3") (pinfunction "/LIN_3") (pintype "input"))
    )
    (net (code "31") (name "Net-(IC5B-G)") (class "Default")
      (node (ref "IC5") (pin "19") (pinfunction "G_19") (pintype "input"))
      (node (ref "JP2") (pin "3") (pinfunction "3_3") (pintype "passive"))
      (node (ref "R29") (pin "2") (pinfunction "2_2") (pintype "passive"))
    )
    (net (code "32") (name "Net-(LED1-PadA)") (class "Default")
      (node (ref "LED1") (pin "A") (pinfunction "A_A") (pintype "passive"))
      (node (ref "R2") (pin "1") (pinfunction "1_1") (pintype "passive"))
    )
    (net (code "33") (name "Net-(LED2-PadC)") (class "Default")
      (node (ref "LED2") (pin "C") (pinfunction "C_C") (pintype "passive"))
      (node (ref "R26") (pin "1") (pinfunction "1_1") (pintype "passive"))
    )
    (net (code "34") (name "Net-(LED3-PadC)") (class "Default")
      (node (ref "LED3") (pin "C") (pinfunction "C_C") (pintype "passive"))
      (node (ref "R27") (pin "1") (pinfunction "1_1") (pintype "passive"))
    )
    (net (code "35") (name "Net-(LED4-PadC)") (class "Default")
      (node (ref "LED4") (pin "C") (pinfunction "C_C") (pintype "passive"))
      (node (ref "R28") (pin "1") (pinfunction "1_1") (pintype "passive"))
    )
    (net (code "36") (name "Net-(PAD3-P)") (class "Default")
      (node (ref "PAD3") (pin "1") (pinfunction "P_1") (pintype "passive"))
      (node (ref "VREG1") (pin "1") (pinfunction "VIN_1") (pintype "bidirectional"))
      (node (ref "VREG2") (pin "1") (pinfunction "VIN_1") (pintype "bidirectional"))
      (node (ref "VREG3") (pin "1") (pinfunction "VIN_1") (pintype "bidirectional"))
    )
    (net (code "37") (name "Net-(PAD4-P)") (class "Default")
      (node (ref "D23") (pin "C") (pinfunction "C_C") (pintype "passive"))
      (node (ref "PAD4") (pin "1") (pinfunction "P_1") (pintype "passive"))
    )
    (net (code "38") (name "Net-(T1-D)") (class "Default")
      (node (ref "D1") (pin "C") (pinfunction "C_C") (pintype "passive"))
      (node (ref "D11") (pin "C") (pinfunction "C_C") (pintype "passive"))
      (node (ref "IC3") (pin "IP-") (pinfunction "IP-_IP-") (pintype "passive"))
      (node (ref "IC3") (pin "IP-@10") (pinfunction "IP-_IP-@10") (pintype "passive"))
      (node (ref "IC3") (pin "IP-@11") (pinfunction "IP-_IP-@11") (pintype "passive"))
      (node (ref "IC3") (pin "IP-@12") (pinfunction "IP-_IP-@12") (pintype "passive"))
      (node (ref "IC3") (pin "IP-@13") (pinfunction "IP-_IP-@13") (pintype "passive"))
      (node (ref "IC3") (pin "IP-@14") (pinfunction "IP-_IP-@14") (pintype "passive"))
      (node (ref "IC3") (pin "IP-@15") (pinfunction "IP-_IP-@15") (pintype "passive"))
      (node (ref "IC3") (pin "IP-@16") (pinfunction "IP-_IP-@16") (pintype "passive"))
      (node (ref "IC3") (pin "IP-@17") (pinfunction "IP-_IP-@17") (pintype "passive"))
      (node (ref "IC3") (pin "IP-@2") (pinfunction "IP-_IP-@2") (pintype "passive"))
      (node (ref "IC3") (pin "IP-@3") (pinfunction "IP-_IP-@3") (pintype "passive"))
      (node (ref "IC3") (pin "IP-@4") (pinfunction "IP-_IP-@4") (pintype "passive"))
      (node (ref "IC3") (pin "IP-@5") (pinfunction "IP-_IP-@5") (pintype "passive"))
      (node (ref "IC3") (pin "IP-@6") (pinfunction "IP-_IP-@6") (pintype "passive"))
      (node (ref "IC3") (pin "IP-@7") (pinfunction "IP-_IP-@7") (pintype "passive"))
      (node (ref "IC3") (pin "IP-@8") (pinfunction "IP-_IP-@8") (pintype "passive"))
      (node (ref "IC3") (pin "IP-@9") (pinfunction "IP-_IP-@9") (pintype "passive"))
      (node (ref "T1") (pin "4") (pinfunction "D_4") (pintype "passive"))
      (node (ref "T3") (pin "4") (pinfunction "D_4") (pintype "passive"))
    )
    (net (code "39") (name "Net-(T1-G)") (class "Default")
      (node (ref "D3") (pin "C") (pinfunction "C_C") (pintype "passive"))
      (node (ref "R4") (pin "1") (pinfunction "1_1") (pintype "passive"))
      (node (ref "R7") (pin "1") (pinfunction "1_1") (pintype "passive"))
      (node (ref "T1") (pin "1") (pinfunction "G_1") (pintype "passive"))
    )
    (net (code "40") (name "Net-(T2-D)") (class "Default")
      (node (ref "C5") (pin "-") (pinfunction "-_-") (pintype "passive"))
      (node (ref "D1") (pin "A") (pinfunction "A_A") (pintype "passive"))
      (node (ref "D5") (pin "C") (pinfunction "C_C") (pintype "passive"))
      (node (ref "R7") (pin "2") (pinfunction "2_2") (pintype "passive"))
      (node (ref "T1") (pin "2") (pinfunction "S_2") (pintype "passive"))
      (node (ref "T1") (pin "3") (pinfunction "S_3") (pintype "passive"))
      (node (ref "T1") (pin "5") (pinfunction "S_5") (pintype "passive"))
      (node (ref "T1") (pin "6") (pinfunction "S_6") (pintype "passive"))
      (node (ref "T1") (pin "7") (pinfunction "S_7") (pintype "passive"))
      (node (ref "T2") (pin "4") (pinfunction "D_4") (pintype "passive"))
      (node (ref "TP2") (pin "TP") (pinfunction "TP_TP") (pintype "input"))
      (node (ref "U1") (pin "6") (pinfunction "VS_6") (pintype "output"))
    )
    (net (code "41") (name "Net-(T2-G)") (class "Default")
      (node (ref "D4") (pin "C") (pinfunction "C_C") (pintype "passive"))
      (node (ref "R5") (pin "1") (pinfunction "1_1") (pintype "passive"))
      (node (ref "R6") (pin "1") (pinfunction "1_1") (pintype "passive"))
      (node (ref "T2") (pin "1") (pinfunction "G_1") (pintype "passive"))
    )
    (net (code "42") (name "Net-(T3-G)") (class "Default")
      (node (ref "D14") (pin "C") (pinfunction "C_C") (pintype "passive"))
      (node (ref "R14") (pin "1") (pinfunction "1_1") (pintype "passive"))
      (node (ref "R17") (pin "1") (pinfunction "1_1") (pintype "passive"))
      (node (ref "T3") (pin "1") (pinfunction "G_1") (pintype "passive"))
    )
    (net (code "43") (name "Net-(T4-D)") (class "Default")
      (node (ref "C7") (pin "-") (pinfunction "-_-") (pintype "passive"))
      (node (ref "D11") (pin "A") (pinfunction "A_A") (pintype "passive"))
      (node (ref "D15") (pin "C") (pinfunction "C_C") (pintype "passive"))
      (node (ref "R17") (pin "2") (pinfunction "2_2") (pintype "passive"))
      (node (ref "T3") (pin "2") (pinfunction "S_2") (pintype "passive"))
      (node (ref "T3") (pin "3") (pinfunction "S_3") (pintype "passive"))
      (node (ref "T3") (pin "5") (pinfunction "S_5") (pintype "passive"))
      (node (ref "T3") (pin "6") (pinfunction "S_6") (pintype "passive"))
      (node (ref "T3") (pin "7") (pinfunction "S_7") (pintype "passive"))
      (node (ref "T4") (pin "4") (pinfunction "D_4") (pintype "passive"))
      (node (ref "TP1") (pin "TP") (pinfunction "TP_TP") (pintype "input"))
      (node (ref "U3") (pin "6") (pinfunction "VS_6") (pintype "output"))
    )
    (net (code "44") (name "Net-(T4-G)") (class "Default")
      (node (ref "D13") (pin "C") (pinfunction "C_C") (pintype "passive"))
      (node (ref "R15") (pin "1") (pinfunction "1_1") (pintype "passive"))
      (node (ref "R16") (pin "1") (pinfunction "1_1") (pintype "passive"))
      (node (ref "T4") (pin "1") (pinfunction "G_1") (pintype "passive"))
    )
    (net (code "45") (name "Net-(T5-D)") (class "Default")
      (node (ref "D16") (pin "C") (pinfunction "C_C") (pintype "passive"))
      (node (ref "D6") (pin "C") (pinfunction "C_C") (pintype "passive"))
      (node (ref "IC2") (pin "IP-") (pinfunction "IP-_IP-") (pintype "passive"))
      (node (ref "IC2") (pin "IP-@10") (pinfunction "IP-_IP-@10") (pintype "passive"))
      (node (ref "IC2") (pin "IP-@11") (pinfunction "IP-_IP-@11") (pintype "passive"))
      (node (ref "IC2") (pin "IP-@12") (pinfunction "IP-_IP-@12") (pintype "passive"))
      (node (ref "IC2") (pin "IP-@13") (pinfunction "IP-_IP-@13") (pintype "passive"))
      (node (ref "IC2") (pin "IP-@14") (pinfunction "IP-_IP-@14") (pintype "passive"))
      (node (ref "IC2") (pin "IP-@15") (pinfunction "IP-_IP-@15") (pintype "passive"))
      (node (ref "IC2") (pin "IP-@16") (pinfunction "IP-_IP-@16") (pintype "passive"))
      (node (ref "IC2") (pin "IP-@17") (pinfunction "IP-_IP-@17") (pintype "passive"))
      (node (ref "IC2") (pin "IP-@2") (pinfunction "IP-_IP-@2") (pintype "passive"))
      (node (ref "IC2") (pin "IP-@3") (pinfunction "IP-_IP-@3") (pintype "passive"))
      (node (ref "IC2") (pin "IP-@4") (pinfunction "IP-_IP-@4") (pintype "passive"))
      (node (ref "IC2") (pin "IP-@5") (pinfunction "IP-_IP-@5") (pintype "passive"))
      (node (ref "IC2") (pin "IP-@6") (pinfunction "IP-_IP-@6") (pintype "passive"))
      (node (ref "IC2") (pin "IP-@7") (pinfunction "IP-_IP-@7") (pintype "passive"))
      (node (ref "IC2") (pin "IP-@8") (pinfunction "IP-_IP-@8") (pintype "passive"))
      (node (ref "IC2") (pin "IP-@9") (pinfunction "IP-_IP-@9") (pintype "passive"))
      (node (ref "T5") (pin "4") (pinfunction "D_4") (pintype "passive"))
      (node (ref "T7") (pin "4") (pinfunction "D_4") (pintype "passive"))
    )
    (net (code "46") (name "Net-(T5-G)") (class "Default")
      (node (ref "D9") (pin "C") (pinfunction "C_C") (pintype "passive"))
      (node (ref "R12") (pin "1") (pinfunction "1_1") (pintype "passive"))
      (node (ref "R9") (pin "1") (pinfunction "1_1") (pintype "passive"))
      (node (ref "T5") (pin "1") (pinfunction "G_1") (pintype "passive"))
    )
    (net (code "47") (name "Net-(T6-D)") (class "Default")
      (node (ref "C6") (pin "-") (pinfunction "-_-") (pintype "passive"))
      (node (ref "D10") (pin "C") (pinfunction "C_C") (pintype "passive"))
      (node (ref "D6") (pin "A") (pinfunction "A_A") (pintype "passive"))
      (node (ref "R12") (pin "2") (pinfunction "2_2") (pintype "passive"))
      (node (ref "T5") (pin "2") (pinfunction "S_2") (pintype "passive"))
      (node (ref "T5") (pin "3") (pinfunction "S_3") (pintype "passive"))
      (node (ref "T5") (pin "5") (pinfunction "S_5") (pintype "passive"))
      (node (ref "T5") (pin "6") (pinfunction "S_6") (pintype "passive"))
      (node (ref "T5") (pin "7") (pinfunction "S_7") (pintype "passive"))
      (node (ref "T6") (pin "4") (pinfunction "D_4") (pintype "passive"))
      (node (ref "TP4") (pin "TP") (pinfunction "TP_TP") (pintype "input"))
      (node (ref "U2") (pin "6") (pinfunction "VS_6") (pintype "output"))
    )
    (net (code "48") (name "Net-(T6-G)") (class "Default")
      (node (ref "D8") (pin "C") (pinfunction "C_C") (pintype "passive"))
      (node (ref "R10") (pin "1") (pinfunction "1_1") (pintype "passive"))
      (node (ref "R11") (pin "1") (pinfunction "1_1") (pintype "passive"))
      (node (ref "T6") (pin "1") (pinfunction "G_1") (pintype "passive"))
    )
    (net (code "49") (name "Net-(T7-G)") (class "Default")
      (node (ref "D19") (pin "C") (pinfunction "C_C") (pintype "passive"))
      (node (ref "R19") (pin "1") (pinfunction "1_1") (pintype "passive"))
      (node (ref "R22") (pin "1") (pinfunction "1_1") (pintype "passive"))
      (node (ref "T7") (pin "1") (pinfunction "G_1") (pintype "passive"))
    )
    (net (code "50") (name "Net-(T8-D)") (class "Default")
      (node (ref "C8") (pin "-") (pinfunction "-_-") (pintype "passive"))
      (node (ref "D16") (pin "A") (pinfunction "A_A") (pintype "passive"))
      (node (ref "D20") (pin "C") (pinfunction "C_C") (pintype "passive"))
      (node (ref "R22") (pin "2") (pinfunction "2_2") (pintype "passive"))
      (node (ref "T7") (pin "2") (pinfunction "S_2") (pintype "passive"))
      (node (ref "T7") (pin "3") (pinfunction "S_3") (pintype "passive"))
      (node (ref "T7") (pin "5") (pinfunction "S_5") (pintype "passive"))
      (node (ref "T7") (pin "6") (pinfunction "S_6") (pintype "passive"))
      (node (ref "T7") (pin "7") (pinfunction "S_7") (pintype "passive"))
      (node (ref "T8") (pin "4") (pinfunction "D_4") (pintype "passive"))
      (node (ref "TP3") (pin "TP") (pinfunction "TP_TP") (pintype "input"))
      (node (ref "U4") (pin "6") (pinfunction "VS_6") (pintype "output"))
    )
    (net (code "51") (name "Net-(T8-G)") (class "Default")
      (node (ref "D18") (pin "C") (pinfunction "C_C") (pintype "passive"))
      (node (ref "R20") (pin "1") (pinfunction "1_1") (pintype "passive"))
      (node (ref "R21") (pin "1") (pinfunction "1_1") (pintype "passive"))
      (node (ref "T8") (pin "1") (pinfunction "G_1") (pintype "passive"))
    )
    (net (code "52") (name "Net-(U1-HO)") (class "Default")
      (node (ref "D3") (pin "A") (pinfunction "A_A") (pintype "passive"))
      (node (ref "R4") (pin "2") (pinfunction "2_2") (pintype "passive"))
      (node (ref "U1") (pin "7") (pinfunction "HO_7") (pintype "output"))
    )
    (net (code "53") (name "Net-(U1-LO)") (class "Default")
      (node (ref "D4") (pin "A") (pinfunction "A_A") (pintype "passive"))
      (node (ref "R5") (pin "2") (pinfunction "2_2") (pintype "passive"))
      (node (ref "U1") (pin "5") (pinfunction "LO_5") (pintype "output"))
    )
    (net (code "54") (name "Net-(U2-HO)") (class "Default")
      (node (ref "D9") (pin "A") (pinfunction "A_A") (pintype "passive"))
      (node (ref "R9") (pin "2") (pinfunction "2_2") (pintype "passive"))
      (node (ref "U2") (pin "7") (pinfunction "HO_7") (pintype "output"))
    )
    (net (code "55") (name "Net-(U2-LO)") (class "Default")
      (node (ref "D8") (pin "A") (pinfunction "A_A") (pintype "passive"))
      (node (ref "R10") (pin "2") (pinfunction "2_2") (pintype "passive"))
      (node (ref "U2") (pin "5") (pinfunction "LO_5") (pintype "output"))
    )
    (net (code "56") (name "Net-(U3-HO)") (class "Default")
      (node (ref "D14") (pin "A") (pinfunction "A_A") (pintype "passive"))
      (node (ref "R14") (pin "2") (pinfunction "2_2") (pintype "passive"))
      (node (ref "U3") (pin "7") (pinfunction "HO_7") (pintype "output"))
    )
    (net (code "57") (name "Net-(U3-LO)") (class "Default")
      (node (ref "D13") (pin "A") (pinfunction "A_A") (pintype "passive"))
      (node (ref "R15") (pin "2") (pinfunction "2_2") (pintype "passive"))
      (node (ref "U3") (pin "5") (pinfunction "LO_5") (pintype "output"))
    )
    (net (code "58") (name "Net-(U4-HO)") (class "Default")
      (node (ref "D19") (pin "A") (pinfunction "A_A") (pintype "passive"))
      (node (ref "R19") (pin "2") (pinfunction "2_2") (pintype "passive"))
      (node (ref "U4") (pin "7") (pinfunction "HO_7") (pintype "output"))
    )
    (net (code "59") (name "Net-(U4-LO)") (class "Default")
      (node (ref "D18") (pin "A") (pinfunction "A_A") (pintype "passive"))
      (node (ref "R20") (pin "2") (pinfunction "2_2") (pintype "passive"))
      (node (ref "U4") (pin "5") (pinfunction "LO_5") (pintype "output"))
    )
    (net (code "60") (name "Net-(VREG3-VOUT)") (class "Default")
      (node (ref "C16") (pin "2") (pinfunction "2_2") (pintype "passive"))
      (node (ref "C23") (pin "+") (pinfunction "+_+") (pintype "passive"))
      (node (ref "JP2") (pin "7") (pinfunction "7_7") (pintype "passive"))
      (node (ref "VREG3") (pin "3") (pinfunction "VOUT_3") (pintype "bidirectional"))
    )
    (net (code "61") (name "VCC") (class "Default")
      (node (ref "C12") (pin "+") (pinfunction "+_+") (pintype "passive"))
      (node (ref "C14") (pin "2") (pinfunction "2_2") (pintype "passive"))
      (node (ref "C3") (pin "+") (pinfunction "+_+") (pintype "passive"))
      (node (ref "C4") (pin "2") (pinfunction "2_2") (pintype "passive"))
      (node (ref "IC1") (pin "18") (pinfunction "AVCC_18") (pintype "power_in"))
      (node (ref "IC1") (pin "4") (pinfunction "VCC_4") (pintype "power_in"))
      (node (ref "IC1") (pin "6") (pinfunction "VCC_6") (pintype "power_in"))
      (node (ref "IC2") (pin "1") (pinfunction "VCC_1") (pintype "power_in"))
      (node (ref "IC3") (pin "1") (pinfunction "VCC_1") (pintype "power_in"))
      (node (ref "IC5") (pin "11") (pinfunction "A1_11") (pintype "input"))
      (node (ref "IC5") (pin "20") (pinfunction "VCC_20") (pintype "power_in"))
      (node (ref "JP1") (pin "2") (pinfunction "2_2") (pintype "passive"))
      (node (ref "JP2") (pin "6") (pinfunction "6_6") (pintype "passive"))
      (node (ref "R1") (pin "1") (pinfunction "1_1") (pintype "passive"))
      (node (ref "R13") (pin "2") (pinfunction "2_2") (pintype "passive"))
      (node (ref "R18") (pin "2") (pinfunction "2_2") (pintype "passive"))
      (node (ref "R2") (pin "2") (pinfunction "2_2") (pintype "passive"))
      (node (ref "R3") (pin "2") (pinfunction "2_2") (pintype "passive"))
      (node (ref "R8") (pin "2") (pinfunction "2_2") (pintype "passive"))
      (node (ref "VREG1") (pin "3") (pinfunction "VOUT_3") (pintype "bidirectional"))
    )
    (net (code "62") (name "VCCINT") (class "Default")
      (node (ref "C11") (pin "+") (pinfunction "+_+") (pintype "passive"))
      (node (ref "C13") (pin "2") (pinfunction "2_2") (pintype "passive"))
      (node (ref "D12") (pin "A") (pinfunction "A_A") (pintype "passive"))
      (node (ref "D17") (pin "A") (pinfunction "A_A") (pintype "passive"))
      (node (ref "D2") (pin "A") (pinfunction "A_A") (pintype "passive"))
      (node (ref "D7") (pin "A") (pinfunction "A_A") (pintype "passive"))
      (node (ref "U1") (pin "1") (pinfunction "VCC_1") (pintype "power_in"))
      (node (ref "U2") (pin "1") (pinfunction "VCC_1") (pintype "power_in"))
      (node (ref "U3") (pin "1") (pinfunction "VCC_1") (pintype "power_in"))
      (node (ref "U4") (pin "1") (pinfunction "VCC_1") (pintype "power_in"))
      (node (ref "VREG2") (pin "3") (pinfunction "VOUT_3") (pintype "bidirectional"))
    )
    (net (code "63") (name "unconnected-(IC1-AREF-Pad20)") (class "Default")
      (node (ref "IC1") (pin "20") (pinfunction "AREF_20") (pintype "passive"))
    )
    (net (code "64") (name "unconnected-(IC1-PB0(ICP)-Pad12)") (class "Default")
      (node (ref "IC1") (pin "12") (pinfunction "PB0(ICP)_12") (pintype "bidirectional"))
    )
    (net (code "65") (name "unconnected-(IC1-PB1(OC1A)-Pad13)") (class "Default")
      (node (ref "IC1") (pin "13") (pinfunction "PB1(OC1A)_13") (pintype "bidirectional"))
    )
    (net (code "66") (name "unconnected-(IC1-PB2(SS{slash}OC1B)-Pad14)") (class "Default")
      (node (ref "IC1") (pin "14") (pinfunction "PB2(SS/OC1B)_14") (pintype "bidirectional"))
    )
    (net (code "67") (name "unconnected-(IC1-PC3(ADC3)-Pad26)") (class "Default")
      (node (ref "IC1") (pin "26") (pinfunction "PC3(ADC3)_26") (pintype "bidirectional"))
    )
    (net (code "68") (name "unconnected-(IC1-PD1(TXD)-Pad31)") (class "Default")
      (node (ref "IC1") (pin "31") (pinfunction "PD1(TXD)_31") (pintype "bidirectional"))
    )
    (net (code "69") (name "unconnected-(IC1-PD2(INT0)-Pad32)") (class "Default")
      (node (ref "IC1") (pin "32") (pinfunction "PD2(INT0)_32") (pintype "bidirectional"))
    )
    (net (code "70") (name "unconnected-(IC1-PD4(XCK{slash}T0)-Pad2)") (class "Default")
      (node (ref "IC1") (pin "2") (pinfunction "PD4(XCK/T0)_2") (pintype "bidirectional"))
    )
    (net (code "71") (name "unconnected-(IC1-PD7(AIN1)-Pad11)") (class "Default")
      (node (ref "IC1") (pin "11") (pinfunction "PD7(AIN1)_11") (pintype "bidirectional"))
    )
    (net (code "72") (name "unconnected-(IC5B-A2-Pad13)") (class "Default")
      (node (ref "IC5") (pin "13") (pinfunction "A2_13") (pintype "input"))
    )
    (net (code "73") (name "unconnected-(IC5B-A3-Pad15)") (class "Default")
      (node (ref "IC5") (pin "15") (pinfunction "A3_15") (pintype "input"))
    )
    (net (code "74") (name "unconnected-(IC5B-A4-Pad17)") (class "Default")
      (node (ref "IC5") (pin "17") (pinfunction "A4_17") (pintype "input"))
    )
    (net (code "75") (name "unconnected-(IC5B-Y2-Pad7)") (class "Default")
      (node (ref "IC5") (pin "7") (pinfunction "Y2_7") (pintype "tri_state"))
    )
    (net (code "76") (name "unconnected-(IC5B-Y3-Pad5)") (class "Default")
      (node (ref "IC5") (pin "5") (pinfunction "Y3_5") (pintype "tri_state"))
    )
    (net (code "77") (name "unconnected-(IC5B-Y4-Pad3)") (class "Default")
      (node (ref "IC5") (pin "3") (pinfunction "Y4_3") (pintype "tri_state"))
    )
    (net (code "78") (name "unconnected-(JP2-Pad5)") (class "Default")
      (node (ref "JP2") (pin "5") (pinfunction "5_5") (pintype "passive"))
    )
  )
)
